# Buck_Converter_Reference_Board_5V_3A_LM2.net
KiCad netlist of a schematic drawn in EAGLE
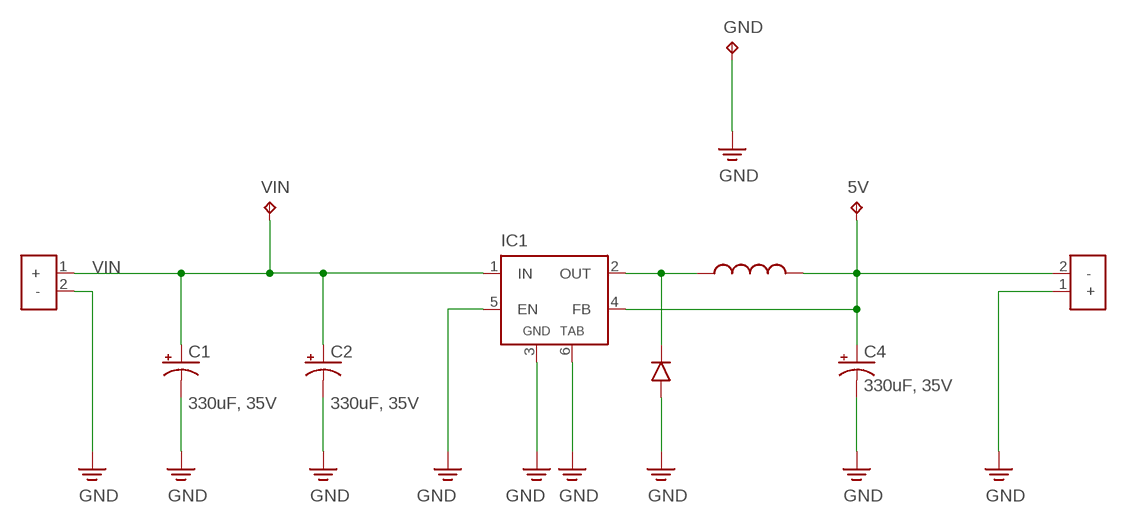
[diagram p0: schematic, sheet 1]

(export (version "E")
  (design (tool "Eeschema 10.0.6"))
  (components
    (comp (ref "5V")
      (value "TPPAD1-13")
      (footprint "eagle-import:P1-13")
      (libsource (lib "eagle-import") (part "TPPAD1-13"))
    )
    (comp (ref "C1")
      (value "330uF, 35V")
      (footprint "eagle-import:_CAPACITOR_CHEMI-CON_A_HA0_SMD")
      (libsource (lib "eagle-import") (part "_CAPACITOR_POL_A_HA0"))
    )
    (comp (ref "C2")
      (value "330uF, 35V")
      (footprint "eagle-import:_CAPACITOR_CHEMI-CON_A_HA0_SMD")
      (libsource (lib "eagle-import") (part "_CAPACITOR_POL_A_HA0"))
    )
    (comp (ref "C4")
      (value "330uF, 35V")
      (footprint "eagle-import:_CAPACITOR_CHEMI-CON_A_HA0_SMD")
      (libsource (lib "eagle-import") (part "_CAPACITOR_POL_A_HA0"))
    )
    (comp (ref "GND")
      (value "TPPAD1-13")
      (footprint "eagle-import:P1-13")
      (libsource (lib "eagle-import") (part "TPPAD1-13"))
    )
    (comp (ref "IC1")
      (value "_VOLTAG_REGULATOR_LM2596S")
      (footprint "eagle-import:_PACKAGE_TO263-5")
      (libsource (lib "eagle-import") (part "_VOLTAG_REGULATOR_LM2596S"))
    )
    (comp (ref "U$1")
      (value "POWER_CONNECTOR")
      (footprint "eagle-import:_TERMINAL_BLOCK_2.54_1X2")
      (libsource (lib "eagle-import") (part "POWER_CONNECTOR"))
    )
    (comp (ref "U$22")
      (value "POWER_CONNECTOR")
      (footprint "eagle-import:_TERMINAL_BLOCK_2.54_1X2")
      (libsource (lib "eagle-import") (part "POWER_CONNECTOR"))
    )
    (comp (ref "U$23")
      (value "_INDUCTOR_PE-54040SNL")
      (footprint "eagle-import:_PACKAGE_HCI-68")
      (libsource (lib "eagle-import") (part "_INDUCTOR_PE-54040SNL"))
    )
    (comp (ref "U$24")
      (value "_DIODE_SOD128")
      (footprint "eagle-import:_PACKAGE_SOD128")
      (libsource (lib "eagle-import") (part "_DIODE_SOD128"))
    )
    (comp (ref "VIN")
      (value "TPPAD1-13")
      (footprint "eagle-import:P1-13")
      (libsource (lib "eagle-import") (part "TPPAD1-13"))
    )
  )
  (nets
    (net (code "1") (name "/VIN") (class "Default")
      (node (ref "C1") (pin "+") (pinfunction "+_+") (pintype "passive"))
      (node (ref "C2") (pin "+") (pinfunction "+_+") (pintype "passive"))
      (node (ref "IC1") (pin "1") (pinfunction "IN_1") (pintype "input"))
      (node (ref "U$22") (pin "1") (pinfunction "+_1") (pintype "bidirectional"))
      (node (ref "VIN") (pin "TP") (pinfunction "TP_TP") (pintype "input"))
    )
    (net (code "2") (name "GND") (class "Default")
      (node (ref "C1") (pin "-") (pinfunction "-_-") (pintype "passive"))
      (node (ref "C2") (pin "-") (pinfunction "-_-") (pintype "passive"))
      (node (ref "C4") (pin "-") (pinfunction "-_-") (pintype "passive"))
      (node (ref "GND") (pin "TP") (pinfunction "TP_TP") (pintype "input"))
      (node (ref "IC1") (pin "3") (pinfunction "GND_3") (pintype "power_in"))
      (node (ref "IC1") (pin "5") (pinfunction "EN_5") (pintype "input"))
      (node (ref "IC1") (pin "6") (pinfunction "TAB_6") (pintype "power_in"))
      (node (ref "U$1") (pin "1") (pinfunction "+_1") (pintype "bidirectional"))
      (node (ref "U$22") (pin "2") (pinfunction "-_2") (pintype "bidirectional"))
      (node (ref "U$24") (pin "A") (pinfunction "+_A") (pintype "input"))
    )
    (net (code "3") (name "Net-(IC1-FB)") (class "Default")
      (node (ref "5V") (pin "TP") (pinfunction "TP_TP") (pintype "input"))
      (node (ref "C4") (pin "+") (pinfunction "+_+") (pintype "passive"))
      (node (ref "IC1") (pin "4") (pinfunction "FB_4") (pintype "input"))
      (node (ref "U$1") (pin "2") (pinfunction "-_2") (pintype "bidirectional"))
      (node (ref "U$23") (pin "2") (pinfunction "2_2") (pintype "bidirectional"))
    )
    (net (code "4") (name "Net-(IC1-OUT)") (class "Default")
      (node (ref "IC1") (pin "2") (pinfunction "OUT_2") (pintype "output"))
      (node (ref "U$23") (pin "1") (pinfunction "1_1") (pintype "bidirectional"))
      (node (ref "U$24") (pin "C") (pinfunction "-_C") (pintype "output"))
    )
  )
)
